# Main.net
KiCad netlist of a schematic drawn in Altium Designer
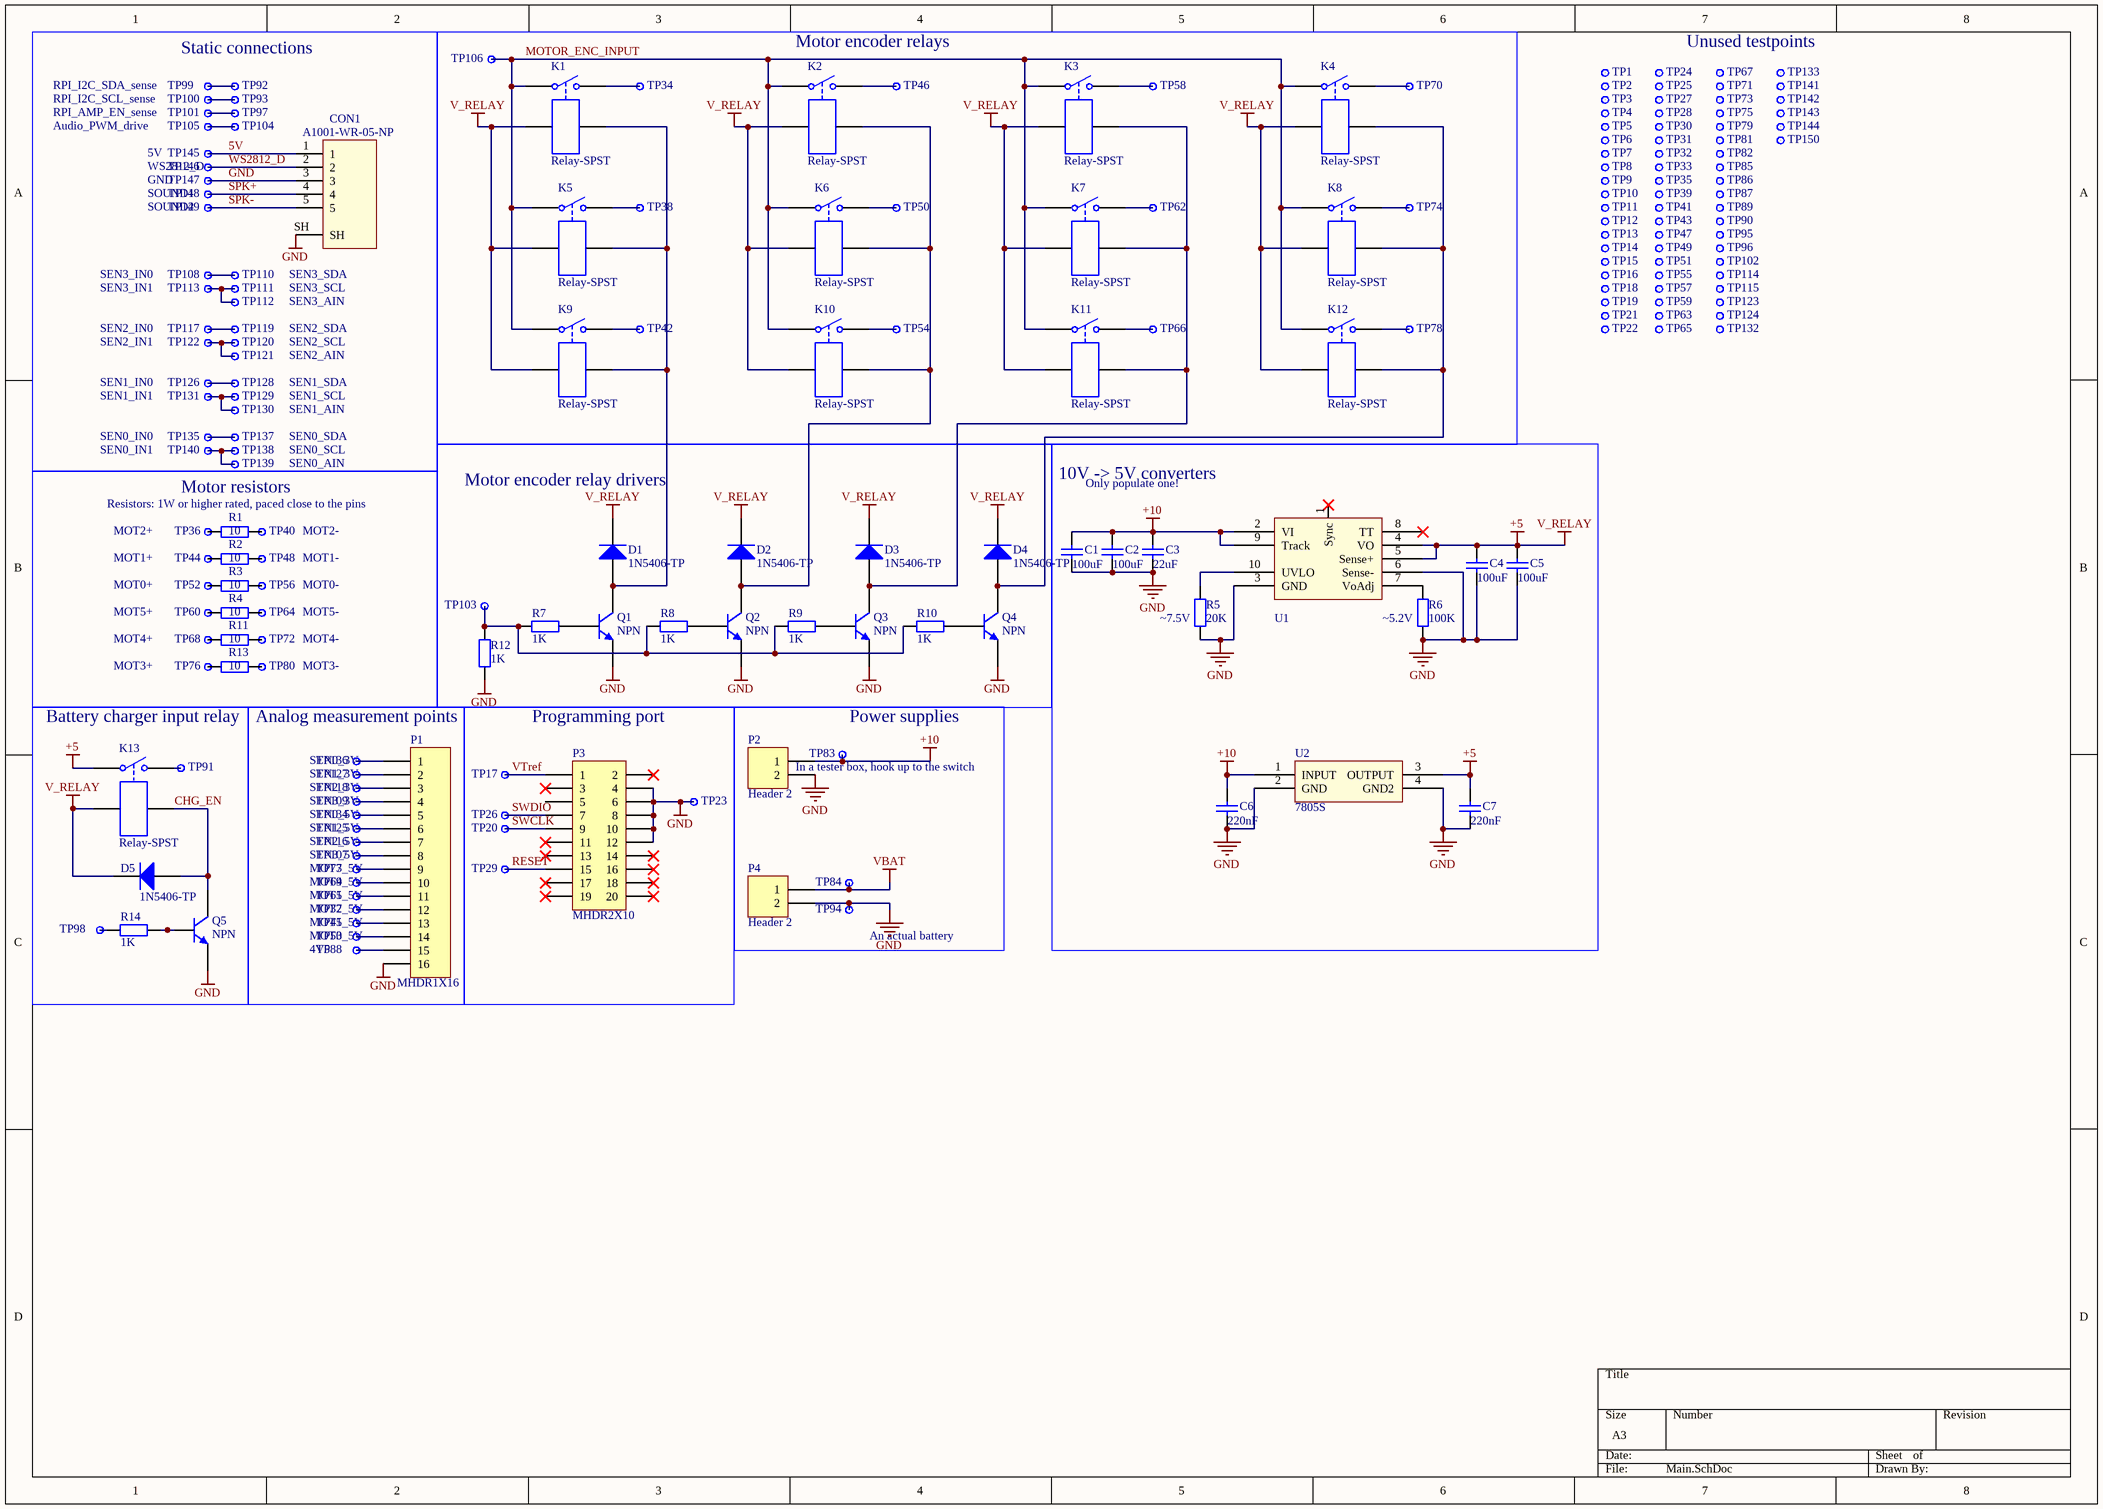
[diagram p0: Main.SchDoc]

(export (version "E")
  (design (tool "Eeschema 10.0.6"))
  (components
    (comp (ref "C1")
      (value "100uF")
      (footprint "C3216")
      (description "Capacitor")
      (fields (field (name "PARTNUMBER") "CL31A107MPKNNWE") (field (name "PUBLISHER") "Altium Limited"))
      (libsource (lib "Miscellaneous Devices") (part "Cap"))
    )
    (comp (ref "C2")
      (value "100uF")
      (footprint "C3216")
      (description "Capacitor")
      (fields (field (name "PARTNUMBER") "CL31A107MPKNNWE") (field (name "PUBLISHER") "Altium Limited"))
      (libsource (lib "Miscellaneous Devices") (part "Cap"))
    )
    (comp (ref "C3")
      (value "22uF")
      (footprint "6-0805_N")
      (description "Capacitor")
      (fields (field (name "Comment") "Cap") (field (name "PUBLISHER") "Altium Limited"))
      (libsource (lib "Miscellaneous Devices") (part "Cap"))
    )
    (comp (ref "C4")
      (value "100uF")
      (footprint "C3216")
      (description "Capacitor")
      (fields (field (name "PARTNUMBER") "CL31A107MPKNNWE") (field (name "PUBLISHER") "Altium Limited"))
      (libsource (lib "Miscellaneous Devices") (part "Cap"))
    )
    (comp (ref "C5")
      (value "100uF")
      (footprint "C3216")
      (description "Capacitor")
      (fields (field (name "PARTNUMBER") "CL31A107MPKNNWE") (field (name "PUBLISHER") "Altium Limited"))
      (libsource (lib "Miscellaneous Devices") (part "Cap"))
    )
    (comp (ref "C6")
      (value "220nF")
      (footprint "6-0805_N")
      (description "Capacitor")
      (fields (field (name "Comment") "Cap") (field (name "PUBLISHER") "Altium Limited"))
      (libsource (lib "Miscellaneous Devices") (part "Cap"))
    )
    (comp (ref "C7")
      (value "220nF")
      (footprint "6-0805_N")
      (description "Capacitor")
      (fields (field (name "Comment") "Cap") (field (name "PUBLISHER") "Altium Limited"))
      (libsource (lib "Miscellaneous Devices") (part "Cap"))
    )
    (comp (ref "CON1")
      (value "A1001-WR-05-NP")
      (footprint "LED molex")
      (libsource (lib "parts") (part "LED molex"))
    )
    (comp (ref "D1")
      (value "1N5406-TP")
      (footprint "DO-201AD")
      (fields (field (name "PUBLISHER") "Altium Limited"))
      (libsource (lib "Miscellaneous Devices") (part "Diode"))
    )
    (comp (ref "D2")
      (value "1N5406-TP")
      (footprint "DO-201AD")
      (fields (field (name "PUBLISHER") "Altium Limited"))
      (libsource (lib "Miscellaneous Devices") (part "Diode"))
    )
    (comp (ref "D3")
      (value "1N5406-TP")
      (footprint "DO-201AD")
      (fields (field (name "PUBLISHER") "Altium Limited"))
      (libsource (lib "Miscellaneous Devices") (part "Diode"))
    )
    (comp (ref "D4")
      (value "1N5406-TP")
      (footprint "DO-201AD")
      (fields (field (name "PUBLISHER") "Altium Limited"))
      (libsource (lib "Miscellaneous Devices") (part "Diode"))
    )
    (comp (ref "D5")
      (value "1N5406-TP")
      (footprint "DO-201AD")
      (fields (field (name "PUBLISHER") "Altium Limited"))
      (libsource (lib "Miscellaneous Devices") (part "Diode"))
    )
    (comp (ref "K1")
      (value "Relay-SPST")
      (footprint "AHQSH105LM100G")
      (description "Single-Pole Single-Throw Relay")
      (fields (field (name "PUBLISHER") "Altium Limited"))
      (libsource (lib "Miscellaneous Devices") (part "Relay-SPST"))
    )
    (comp (ref "K2")
      (value "Relay-SPST")
      (footprint "AHQSH105LM100G")
      (description "Single-Pole Single-Throw Relay")
      (fields (field (name "PUBLISHER") "Altium Limited"))
      (libsource (lib "Miscellaneous Devices") (part "Relay-SPST"))
    )
    (comp (ref "K3")
      (value "Relay-SPST")
      (footprint "AHQSH105LM100G")
      (description "Single-Pole Single-Throw Relay")
      (fields (field (name "PUBLISHER") "Altium Limited"))
      (libsource (lib "Miscellaneous Devices") (part "Relay-SPST"))
    )
    (comp (ref "K4")
      (value "Relay-SPST")
      (footprint "AHQSH105LM100G")
      (description "Single-Pole Single-Throw Relay")
      (fields (field (name "PUBLISHER") "Altium Limited"))
      (libsource (lib "Miscellaneous Devices") (part "Relay-SPST"))
    )
    (comp (ref "K5")
      (value "Relay-SPST")
      (footprint "AHQSH105LM100G")
      (description "Single-Pole Single-Throw Relay")
      (fields (field (name "PUBLISHER") "Altium Limited"))
      (libsource (lib "Miscellaneous Devices") (part "Relay-SPST"))
    )
    (comp (ref "K6")
      (value "Relay-SPST")
      (footprint "AHQSH105LM100G")
      (description "Single-Pole Single-Throw Relay")
      (fields (field (name "PUBLISHER") "Altium Limited"))
      (libsource (lib "Miscellaneous Devices") (part "Relay-SPST"))
    )
    (comp (ref "K7")
      (value "Relay-SPST")
      (footprint "AHQSH105LM100G")
      (description "Single-Pole Single-Throw Relay")
      (fields (field (name "PUBLISHER") "Altium Limited"))
      (libsource (lib "Miscellaneous Devices") (part "Relay-SPST"))
    )
    (comp (ref "K8")
      (value "Relay-SPST")
      (footprint "AHQSH105LM100G")
      (description "Single-Pole Single-Throw Relay")
      (fields (field (name "PUBLISHER") "Altium Limited"))
      (libsource (lib "Miscellaneous Devices") (part "Relay-SPST"))
    )
    (comp (ref "K9")
      (value "Relay-SPST")
      (footprint "AHQSH105LM100G")
      (description "Single-Pole Single-Throw Relay")
      (fields (field (name "PUBLISHER") "Altium Limited"))
      (libsource (lib "Miscellaneous Devices") (part "Relay-SPST"))
    )
    (comp (ref "K10")
      (value "Relay-SPST")
      (footprint "AHQSH105LM100G")
      (description "Single-Pole Single-Throw Relay")
      (fields (field (name "PUBLISHER") "Altium Limited"))
      (libsource (lib "Miscellaneous Devices") (part "Relay-SPST"))
    )
    (comp (ref "K11")
      (value "Relay-SPST")
      (footprint "AHQSH105LM100G")
      (description "Single-Pole Single-Throw Relay")
      (fields (field (name "PUBLISHER") "Altium Limited"))
      (libsource (lib "Miscellaneous Devices") (part "Relay-SPST"))
    )
    (comp (ref "K12")
      (value "Relay-SPST")
      (footprint "AHQSH105LM100G")
      (description "Single-Pole Single-Throw Relay")
      (fields (field (name "PUBLISHER") "Altium Limited"))
      (libsource (lib "Miscellaneous Devices") (part "Relay-SPST"))
    )
    (comp (ref "K13")
      (value "Relay-SPST")
      (footprint "AHQSH105LM100G")
      (description "Single-Pole Single-Throw Relay")
      (fields (field (name "PUBLISHER") "Altium Limited"))
      (libsource (lib "Miscellaneous Devices") (part "Relay-SPST"))
    )
    (comp (ref "P1")
      (value "MHDR1X16")
      (footprint "MHDR1X16")
      (description "Header, 16-Pin")
      (fields (field (name "PUBLISHER") "Altium Limited"))
      (libsource (lib "Miscellaneous Connectors") (part "MHDR1X16"))
    )
    (comp (ref "P2")
      (value "Header 2")
      (footprint "HDR1X2")
      (description "Header, 2-Pin")
      (fields (field (name "PUBLISHER") "Altium Limited"))
      (libsource (lib "Miscellaneous Connectors") (part "Header 2"))
    )
    (comp (ref "P3")
      (value "MHDR2X10")
      (footprint "MHDR2X10")
      (description "Header, 10-Pin, Dual row")
      (fields (field (name "PUBLISHER") "Altium Limited"))
      (libsource (lib "Miscellaneous Connectors") (part "MHDR2X10"))
    )
    (comp (ref "P4")
      (value "Header 2")
      (footprint "HDR1X2")
      (description "Header, 2-Pin")
      (fields (field (name "PUBLISHER") "Altium Limited"))
      (libsource (lib "Miscellaneous Connectors") (part "Header 2"))
    )
    (comp (ref "Q1")
      (value "NPN")
      (footprint "SOT-23_N")
      (description "NPN Bipolar Transistor MMBT2222A")
      (fields (field (name "PART NUMBER") "MMBT2222A") (field (name "PUBLISHER") "Altium Limited"))
      (libsource (lib "Miscellaneous Devices") (part "NPN"))
    )
    (comp (ref "Q2")
      (value "NPN")
      (footprint "SOT-23_N")
      (description "NPN Bipolar Transistor MMBT2222A")
      (fields (field (name "PART NUMBER") "MMBT2222A") (field (name "PUBLISHER") "Altium Limited"))
      (libsource (lib "Miscellaneous Devices") (part "NPN"))
    )
    (comp (ref "Q3")
      (value "NPN")
      (footprint "SOT-23_N")
      (description "NPN Bipolar Transistor MMBT2222A")
      (fields (field (name "PART NUMBER") "MMBT2222A") (field (name "PUBLISHER") "Altium Limited"))
      (libsource (lib "Miscellaneous Devices") (part "NPN"))
    )
    (comp (ref "Q4")
      (value "NPN")
      (footprint "SOT-23_N")
      (description "NPN Bipolar Transistor MMBT2222A")
      (fields (field (name "PART NUMBER") "MMBT2222A") (field (name "PUBLISHER") "Altium Limited"))
      (libsource (lib "Miscellaneous Devices") (part "NPN"))
    )
    (comp (ref "Q5")
      (value "NPN")
      (footprint "SOT-23_N")
      (description "NPN Bipolar Transistor MMBT2222A")
      (fields (field (name "PART NUMBER") "MMBT2222A") (field (name "PUBLISHER") "Altium Limited"))
      (libsource (lib "Miscellaneous Devices") (part "NPN"))
    )
    (comp (ref "R1")
      (value "10")
      (footprint "AXIAL-0.7")
      (description "Resistor EP5WS10RJ 10R 5W")
      (fields
        (field (name "PARTNUMBER") "EP5WS10RJ")
        (field (name "Comment") "Res2")
        (field (name "PUBLISHER") "Altium Limited")
      )
      (libsource (lib "Miscellaneous Devices") (part "Res2"))
    )
    (comp (ref "R2")
      (value "10")
      (footprint "AXIAL-0.7")
      (description "Resistor EP5WS10RJ 10R 5W")
      (fields
        (field (name "PARTNUMBER") "EP5WS10RJ")
        (field (name "Comment") "Res2")
        (field (name "PUBLISHER") "Altium Limited")
      )
      (libsource (lib "Miscellaneous Devices") (part "Res2"))
    )
    (comp (ref "R3")
      (value "10")
      (footprint "AXIAL-0.7")
      (description "Resistor EP5WS10RJ 10R 5W")
      (fields
        (field (name "PARTNUMBER") "EP5WS10RJ")
        (field (name "Comment") "Res2")
        (field (name "PUBLISHER") "Altium Limited")
      )
      (libsource (lib "Miscellaneous Devices") (part "Res2"))
    )
    (comp (ref "R4")
      (value "10")
      (footprint "AXIAL-0.7")
      (description "Resistor EP5WS10RJ 10R 5W")
      (fields
        (field (name "PARTNUMBER") "EP5WS10RJ")
        (field (name "Comment") "Res2")
        (field (name "PUBLISHER") "Altium Limited")
      )
      (libsource (lib "Miscellaneous Devices") (part "Res2"))
    )
    (comp (ref "R5")
      (value "20K")
      (footprint "1608[0603]")
      (description "Resistor")
      (fields (field (name "Comment") "Res2") (field (name "PUBLISHER") "Altium Limited"))
      (libsource (lib "") (part "Res2_1"))
    )
    (comp (ref "R6")
      (value "100K")
      (footprint "1608[0603]")
      (description "Resistor")
      (fields (field (name "Comment") "Res2") (field (name "PUBLISHER") "Altium Limited"))
      (libsource (lib "") (part "Res2_1"))
    )
    (comp (ref "R7")
      (value "1K")
      (footprint "1608[0603]")
      (description "Resistor")
      (fields (field (name "Comment") "Res2") (field (name "PUBLISHER") "Altium Limited"))
      (libsource (lib "Miscellaneous Devices") (part "Res2"))
    )
    (comp (ref "R8")
      (value "1K")
      (footprint "1608[0603]")
      (description "Resistor")
      (fields (field (name "Comment") "Res2") (field (name "PUBLISHER") "Altium Limited"))
      (libsource (lib "Miscellaneous Devices") (part "Res2"))
    )
    (comp (ref "R9")
      (value "1K")
      (footprint "1608[0603]")
      (description "Resistor")
      (fields (field (name "Comment") "Res2") (field (name "PUBLISHER") "Altium Limited"))
      (libsource (lib "Miscellaneous Devices") (part "Res2"))
    )
    (comp (ref "R10")
      (value "1K")
      (footprint "1608[0603]")
      (description "Resistor")
      (fields (field (name "Comment") "Res2") (field (name "PUBLISHER") "Altium Limited"))
      (libsource (lib "Miscellaneous Devices") (part "Res2"))
    )
    (comp (ref "R11")
      (value "10")
      (footprint "AXIAL-0.7")
      (description "Resistor EP5WS10RJ 10R 5W")
      (fields
        (field (name "PARTNUMBER") "EP5WS10RJ")
        (field (name "Comment") "Res2")
        (field (name "PUBLISHER") "Altium Limited")
      )
      (libsource (lib "Miscellaneous Devices") (part "Res2"))
    )
    (comp (ref "R12")
      (value "1K")
      (footprint "1608[0603]")
      (description "Resistor")
      (fields (field (name "Comment") "Res2") (field (name "PUBLISHER") "Altium Limited"))
      (libsource (lib "") (part "Res2_1"))
    )
    (comp (ref "R13")
      (value "10")
      (footprint "AXIAL-0.7")
      (description "Resistor EP5WS10RJ 10R 5W")
      (fields
        (field (name "PARTNUMBER") "EP5WS10RJ")
        (field (name "Comment") "Res2")
        (field (name "PUBLISHER") "Altium Limited")
      )
      (libsource (lib "Miscellaneous Devices") (part "Res2"))
    )
    (comp (ref "R14")
      (value "1K")
      (footprint "1608[0603]")
      (description "Resistor")
      (fields (field (name "Comment") "Res2") (field (name "PUBLISHER") "Altium Limited"))
      (libsource (lib "Miscellaneous Devices") (part "Res2"))
    )
    (comp (ref "TP1")
      (value "Pin")
      (footprint "Pin")
      (description "Testing pin")
      (libsource (lib "parts") (part "Pin"))
    )
    (comp (ref "TP2")
      (value "Pin")
      (footprint "Pin")
      (description "Testing pin")
      (libsource (lib "parts") (part "Pin"))
    )
    (comp (ref "TP3")
      (value "Pin")
      (footprint "Pin")
      (description "Testing pin")
      (libsource (lib "parts") (part "Pin"))
    )
    (comp (ref "TP4")
      (value "Pin")
      (footprint "Pin")
      (description "Testing pin")
      (libsource (lib "parts") (part "Pin"))
    )
    (comp (ref "TP5")
      (value "Pin")
      (footprint "Pin")
      (description "Testing pin")
      (libsource (lib "parts") (part "Pin"))
    )
    (comp (ref "TP6")
      (value "Pin")
      (footprint "Pin")
      (description "Testing pin")
      (libsource (lib "parts") (part "Pin"))
    )
    (comp (ref "TP7")
      (value "Pin")
      (footprint "Pin")
      (description "Testing pin")
      (libsource (lib "parts") (part "Pin"))
    )
    (comp (ref "TP8")
      (value "Pin")
      (footprint "Pin")
      (description "Testing pin")
      (libsource (lib "parts") (part "Pin"))
    )
    (comp (ref "TP9")
      (value "Pin")
      (footprint "Pin")
      (description "Testing pin")
      (libsource (lib "parts") (part "Pin"))
    )
    (comp (ref "TP10")
      (value "Pin")
      (footprint "Pin")
      (description "Testing pin")
      (libsource (lib "parts") (part "Pin"))
    )
    (comp (ref "TP11")
      (value "Pin")
      (footprint "Pin")
      (description "Testing pin")
      (libsource (lib "parts") (part "Pin"))
    )
    (comp (ref "TP12")
      (value "Pin")
      (footprint "Pin")
      (description "Testing pin")
      (libsource (lib "parts") (part "Pin"))
    )
    (comp (ref "TP13")
      (value "Pin")
      (footprint "Pin")
      (description "Testing pin")
      (libsource (lib "parts") (part "Pin"))
    )
    (comp (ref "TP14")
      (value "Pin")
      (footprint "Pin")
      (description "Testing pin")
      (libsource (lib "parts") (part "Pin"))
    )
    (comp (ref "TP15")
      (value "Pin")
      (footprint "Pin")
      (description "Testing pin")
      (libsource (lib "parts") (part "Pin"))
    )
    (comp (ref "TP16")
      (value "Pin")
      (footprint "Pin")
      (description "Testing pin")
      (libsource (lib "parts") (part "Pin"))
    )
    (comp (ref "TP17")
      (value "Pin")
      (footprint "Pin")
      (description "Testing pin")
      (libsource (lib "parts") (part "Pin"))
    )
    (comp (ref "TP18")
      (value "Pin")
      (footprint "Pin")
      (description "Testing pin")
      (libsource (lib "parts") (part "Pin"))
    )
    (comp (ref "TP19")
      (value "Pin")
      (footprint "Pin")
      (description "Testing pin")
      (libsource (lib "parts") (part "Pin"))
    )
    (comp (ref "TP20")
      (value "Pin")
      (footprint "Pin")
      (description "Testing pin")
      (libsource (lib "parts") (part "Pin"))
    )
    (comp (ref "TP21")
      (value "Pin")
      (footprint "Pin")
      (description "Testing pin")
      (libsource (lib "parts") (part "Pin"))
    )
    (comp (ref "TP22")
      (value "Pin")
      (footprint "Pin")
      (description "Testing pin")
      (libsource (lib "parts") (part "Pin"))
    )
    (comp (ref "TP23")
      (value "Pin")
      (footprint "Pin")
      (description "Testing pin")
      (libsource (lib "parts") (part "Pin"))
    )
    (comp (ref "TP24")
      (value "Pin")
      (footprint "Pin")
      (description "Testing pin")
      (libsource (lib "parts") (part "Pin"))
    )
    (comp (ref "TP25")
      (value "Pin")
      (footprint "Pin")
      (description "Testing pin")
      (libsource (lib "parts") (part "Pin"))
    )
    (comp (ref "TP26")
      (value "Pin")
      (footprint "Pin")
      (description "Testing pin")
      (libsource (lib "parts") (part "Pin"))
    )
    (comp (ref "TP27")
      (value "Pin")
      (footprint "Pin")
      (description "Testing pin")
      (libsource (lib "parts") (part "Pin"))
    )
    (comp (ref "TP28")
      (value "Pin")
      (footprint "Pin")
      (description "Testing pin")
      (libsource (lib "parts") (part "Pin"))
    )
    (comp (ref "TP29")
      (value "Pin")
      (footprint "Pin")
      (description "Testing pin")
      (libsource (lib "parts") (part "Pin"))
    )
    (comp (ref "TP30")
      (value "Pin")
      (footprint "Pin")
      (description "Testing pin")
      (libsource (lib "parts") (part "Pin"))
    )
    (comp (ref "TP31")
      (value "Pin")
      (footprint "Pin")
      (description "Testing pin")
      (libsource (lib "parts") (part "Pin"))
    )
    (comp (ref "TP32")
      (value "Pin")
      (footprint "Pin")
      (description "Testing pin")
      (libsource (lib "parts") (part "Pin"))
    )
    (comp (ref "TP33")
      (value "Pin")
      (footprint "Pin")
      (description "Testing pin")
      (libsource (lib "parts") (part "Pin"))
    )
    (comp (ref "TP34")
      (value "Pin")
      (footprint "Pin")
      (description "Testing pin")
      (libsource (lib "parts") (part "Pin"))
    )
    (comp (ref "TP35")
      (value "Pin")
      (footprint "Pin")
      (description "Testing pin")
      (libsource (lib "parts") (part "Pin"))
    )
    (comp (ref "TP36")
      (value "Pin")
      (footprint "Pin")
      (description "Testing pin")
      (libsource (lib "parts") (part "Pin"))
    )
    (comp (ref "TP37")
      (value "Pin")
      (footprint "Pin")
      (description "Testing pin")
      (libsource (lib "parts") (part "Pin"))
    )
    (comp (ref "TP38")
      (value "Pin")
      (footprint "Pin")
      (description "Testing pin")
      (libsource (lib "parts") (part "Pin"))
    )
    (comp (ref "TP39")
      (value "Pin")
      (footprint "Pin")
      (description "Testing pin")
      (libsource (lib "parts") (part "Pin"))
    )
    (comp (ref "TP40")
      (value "Pin")
      (footprint "Pin")
      (description "Testing pin")
      (libsource (lib "parts") (part "Pin"))
    )
    (comp (ref "TP41")
      (value "Pin")
      (footprint "Pin")
      (description "Testing pin")
      (libsource (lib "parts") (part "Pin"))
    )
    (comp (ref "TP42")
      (value "Pin")
      (footprint "Pin")
      (description "Testing pin")
      (libsource (lib "parts") (part "Pin"))
    )
    (comp (ref "TP43")
      (value "Pin")
      (footprint "Pin")
      (description "Testing pin")
      (libsource (lib "parts") (part "Pin"))
    )
    (comp (ref "TP44")
      (value "Pin")
      (footprint "Pin")
      (description "Testing pin")
      (libsource (lib "parts") (part "Pin"))
    )
    (comp (ref "TP45")
      (value "Pin")
      (footprint "Pin")
      (description "Testing pin")
      (libsource (lib "parts") (part "Pin"))
    )
    (comp (ref "TP46")
      (value "Pin")
      (footprint "Pin")
      (description "Testing pin")
      (libsource (lib "parts") (part "Pin"))
    )
    (comp (ref "TP47")
      (value "Pin")
      (footprint "Pin")
      (description "Testing pin")
      (libsource (lib "parts") (part "Pin"))
    )
    (comp (ref "TP48")
      (value "Pin")
      (footprint "Pin")
      (description "Testing pin")
      (libsource (lib "parts") (part "Pin"))
    )
    (comp (ref "TP49")
      (value "Pin")
      (footprint "Pin")
      (description "Testing pin")
      (libsource (lib "parts") (part "Pin"))
    )
    (comp (ref "TP50")
      (value "Pin")
      (footprint "Pin")
      (description "Testing pin")
      (libsource (lib "parts") (part "Pin"))
    )
    (comp (ref "TP51")
      (value "Pin")
      (footprint "Pin")
      (description "Testing pin")
      (libsource (lib "parts") (part "Pin"))
    )
    (comp (ref "TP52")
      (value "Pin")
      (footprint "Pin")
      (description "Testing pin")
      (libsource (lib "parts") (part "Pin"))
    )
    (comp (ref "TP53")
      (value "Pin")
      (footprint "Pin")
      (description "Testing pin")
      (libsource (lib "parts") (part "Pin"))
    )
    (comp (ref "TP54")
      (value "Pin")
      (footprint "Pin")
      (description "Testing pin")
      (libsource (lib "parts") (part "Pin"))
    )
    (comp (ref "TP55")
      (value "Pin")
      (footprint "Pin")
      (description "Testing pin")
      (libsource (lib "parts") (part "Pin"))
    )
    (comp (ref "TP56")
      (value "Pin")
      (footprint "Pin")
      (description "Testing pin")
      (libsource (lib "parts") (part "Pin"))
    )
    (comp (ref "TP57")
      (value "Pin")
      (footprint "Pin")
      (description "Testing pin")
      (libsource (lib "parts") (part "Pin"))
    )
    (comp (ref "TP58")
      (value "Pin")
      (footprint "Pin")
      (description "Testing pin")
      (libsource (lib "parts") (part "Pin"))
    )
    (comp (ref "TP59")
      (value "Pin")
      (footprint "Pin")
      (description "Testing pin")
      (libsource (lib "parts") (part "Pin"))
    )
    (comp (ref "TP60")
      (value "Pin")
      (footprint "Pin")
      (description "Testing pin")
      (libsource (lib "parts") (part "Pin"))
    )
    (comp (ref "TP61")
      (value "Pin")
      (footprint "Pin")
      (description "Testing pin")
      (libsource (lib "parts") (part "Pin"))
    )
    (comp (ref "TP62")
      (value "Pin")
      (footprint "Pin")
      (description "Testing pin")
      (libsource (lib "parts") (part "Pin"))
    )
    (comp (ref "TP63")
      (value "Pin")
      (footprint "Pin")
      (description "Testing pin")
      (libsource (lib "parts") (part "Pin"))
    )
    (comp (ref "TP64")
      (value "Pin")
      (footprint "Pin")
      (description "Testing pin")
      (libsource (lib "parts") (part "Pin"))
    )
    (comp (ref "TP65")
      (value "Pin")
      (footprint "Pin")
      (description "Testing pin")
      (libsource (lib "parts") (part "Pin"))
    )
    (comp (ref "TP66")
      (value "Pin")
      (footprint "Pin")
      (description "Testing pin")
      (libsource (lib "parts") (part "Pin"))
    )
    (comp (ref "TP67")
      (value "Pin")
      (footprint "Pin")
      (description "Testing pin")
      (libsource (lib "parts") (part "Pin"))
    )
    (comp (ref "TP68")
      (value "Pin")
      (footprint "Pin")
      (description "Testing pin")
      (libsource (lib "parts") (part "Pin"))
    )
    (comp (ref "TP69")
      (value "Pin")
      (footprint "Pin")
      (description "Testing pin")
      (libsource (lib "parts") (part "Pin"))
    )
    (comp (ref "TP70")
      (value "Pin")
      (footprint "Pin")
      (description "Testing pin")
      (libsource (lib "parts") (part "Pin"))
    )
    (comp (ref "TP71")
      (value "Pin")
      (footprint "Pin")
      (description "Testing pin")
      (libsource (lib "parts") (part "Pin"))
    )
    (comp (ref "TP72")
      (value "Pin")
      (footprint "Pin")
      (description "Testing pin")
      (libsource (lib "parts") (part "Pin"))
    )
    (comp (ref "TP73")
      (value "Pin")
      (footprint "Pin")
      (description "Testing pin")
      (libsource (lib "parts") (part "Pin"))
    )
    (comp (ref "TP74")
      (value "Pin")
      (footprint "Pin")
      (description "Testing pin")
      (libsource (lib "parts") (part "Pin"))
    )
    (comp (ref "TP75")
      (value "Pin")
      (footprint "Pin")
      (description "Testing pin")
      (libsource (lib "parts") (part "Pin"))
    )
    (comp (ref "TP76")
      (value "Pin")
      (footprint "Pin")
      (description "Testing pin")
      (libsource (lib "parts") (part "Pin"))
    )
    (comp (ref "TP77")
      (value "Pin")
      (footprint "Pin")
      (description "Testing pin")
      (libsource (lib "parts") (part "Pin"))
    )
    (comp (ref "TP78")
      (value "Pin")
      (footprint "Pin")
      (description "Testing pin")
      (libsource (lib "parts") (part "Pin"))
    )
    (comp (ref "TP79")
      (value "Pin")
      (footprint "Pin")
      (description "Testing pin")
      (libsource (lib "parts") (part "Pin"))
    )
    (comp (ref "TP80")
      (value "Pin")
      (footprint "Pin")
      (description "Testing pin")
      (libsource (lib "parts") (part "Pin"))
    )
    (comp (ref "TP81")
      (value "Pin")
      (footprint "Pin")
      (description "Testing pin")
      (libsource (lib "parts") (part "Pin"))
    )
    (comp (ref "TP82")
      (value "Pin")
      (footprint "Pin")
      (description "Testing pin")
      (libsource (lib "parts") (part "Pin"))
    )
    (comp (ref "TP83")
      (value "Pin")
      (footprint "Pin")
      (description "Testing pin")
      (libsource (lib "parts") (part "Pin"))
    )
    (comp (ref "TP84")
      (value "Pin")
      (footprint "Pin")
      (description "Testing pin")
      (libsource (lib "parts") (part "Pin"))
    )
    (comp (ref "TP85")
      (value "Pin")
      (footprint "Pin")
      (description "Testing pin")
      (libsource (lib "parts") (part "Pin"))
    )
    (comp (ref "TP86")
      (value "Pin")
      (footprint "Pin")
      (description "Testing pin")
      (libsource (lib "parts") (part "Pin"))
    )
    (comp (ref "TP87")
      (value "Pin")
      (footprint "Pin")
      (description "Testing pin")
      (libsource (lib "parts") (part "Pin"))
    )
    (comp (ref "TP88")
      (value "Pin")
      (footprint "Pin")
      (description "Testing pin")
      (libsource (lib "parts") (part "Pin"))
    )
    (comp (ref "TP89")
      (value "Pin")
      (footprint "Pin")
      (description "Testing pin")
      (libsource (lib "parts") (part "Pin"))
    )
    (comp (ref "TP90")
      (value "Pin")
      (footprint "Pin")
      (description "Testing pin")
      (libsource (lib "parts") (part "Pin"))
    )
    (comp (ref "TP91")
      (value "Pin")
      (footprint "Pin")
      (description "Testing pin")
      (libsource (lib "parts") (part "Pin"))
    )
    (comp (ref "TP92")
      (value "Pin")
      (footprint "Pin")
      (description "Testing pin")
      (libsource (lib "parts") (part "Pin"))
    )
    (comp (ref "TP93")
      (value "Pin")
      (footprint "Pin")
      (description "Testing pin")
      (libsource (lib "parts") (part "Pin"))
    )
    (comp (ref "TP94")
      (value "Pin")
      (footprint "Pin")
      (description "Testing pin")
      (libsource (lib "parts") (part "Pin"))
    )
    (comp (ref "TP95")
      (value "Pin")
      (footprint "Pin")
      (description "Testing pin")
      (libsource (lib "parts") (part "Pin"))
    )
    (comp (ref "TP96")
      (value "Pin")
      (footprint "Pin")
      (description "Testing pin")
      (libsource (lib "parts") (part "Pin"))
    )
    (comp (ref "TP97")
      (value "Pin")
      (footprint "Pin")
      (description "Testing pin")
      (libsource (lib "parts") (part "Pin"))
    )
    (comp (ref "TP98")
      (value "Pin")
      (footprint "Pin")
      (description "Testing pin")
      (libsource (lib "parts") (part "Pin"))
    )
    (comp (ref "TP99")
      (value "Pin")
      (footprint "Pin")
      (description "Testing pin")
      (libsource (lib "parts") (part "Pin"))
    )
    (comp (ref "TP100")
      (value "Pin")
      (footprint "Pin")
      (description "Testing pin")
      (libsource (lib "parts") (part "Pin"))
    )
    (comp (ref "TP101")
      (value "Pin")
      (footprint "Pin")
      (description "Testing pin")
      (libsource (lib "parts") (part "Pin"))
    )
    (comp (ref "TP102")
      (value "Pin")
      (footprint "Pin")
      (description "Testing pin")
      (libsource (lib "parts") (part "Pin"))
    )
    (comp (ref "TP103")
      (value "Pin")
      (footprint "Pin")
      (description "Testing pin")
      (libsource (lib "parts") (part "Pin"))
    )
    (comp (ref "TP104")
      (value "Pin")
      (footprint "Pin")
      (description "Testing pin")
      (libsource (lib "parts") (part "Pin"))
    )
    (comp (ref "TP105")
      (value "Pin")
      (footprint "Pin")
      (description "Testing pin")
      (libsource (lib "parts") (part "Pin"))
    )
    (comp (ref "TP106")
      (value "Pin")
      (footprint "Pin")
      (description "Testing pin")
      (libsource (lib "parts") (part "Pin"))
    )
    (comp (ref "TP107")
      (value "Pin")
      (footprint "Pin")
      (description "Testing pin")
      (libsource (lib "parts") (part "Pin"))
    )
    (comp (ref "TP108")
      (value "Pin")
      (footprint "Pin")
      (description "Testing pin")
      (libsource (lib "parts") (part "Pin"))
    )
    (comp (ref "TP109")
      (value "Pin")
      (footprint "Pin")
      (description "Testing pin")
      (libsource (lib "parts") (part "Pin"))
    )
    (comp (ref "TP110")
      (value "Pin")
      (footprint "Pin")
      (description "Testing pin")
      (libsource (lib "parts") (part "Pin"))
    )
    (comp (ref "TP111")
      (value "Pin")
      (footprint "Pin")
      (description "Testing pin")
      (libsource (lib "parts") (part "Pin"))
    )
    (comp (ref "TP112")
      (value "Pin")
      (footprint "Pin")
      (description "Testing pin")
      (libsource (lib "parts") (part "Pin"))
    )
    (comp (ref "TP113")
      (value "Pin")
      (footprint "Pin")
      (description "Testing pin")
      (libsource (lib "parts") (part "Pin"))
    )
    (comp (ref "TP114")
      (value "Pin")
      (footprint "Pin")
      (description "Testing pin")
      (libsource (lib "parts") (part "Pin"))
    )
    (comp (ref "TP115")
      (value "Pin")
      (footprint "Pin")
      (description "Testing pin")
      (libsource (lib "parts") (part "Pin"))
    )
    (comp (ref "TP116")
      (value "Pin")
      (footprint "Pin")
      (description "Testing pin")
      (libsource (lib "parts") (part "Pin"))
    )
    (comp (ref "TP117")
      (value "Pin")
      (footprint "Pin")
      (description "Testing pin")
      (libsource (lib "parts") (part "Pin"))
    )
    (comp (ref "TP118")
      (value "Pin")
      (footprint "Pin")
      (description "Testing pin")
      (libsource (lib "parts") (part "Pin"))
    )
    (comp (ref "TP119")
      (value "Pin")
      (footprint "Pin")
      (description "Testing pin")
      (libsource (lib "parts") (part "Pin"))
    )
    (comp (ref "TP120")
      (value "Pin")
      (footprint "Pin")
      (description "Testing pin")
      (libsource (lib "parts") (part "Pin"))
    )
    (comp (ref "TP121")
      (value "Pin")
      (footprint "Pin")
      (description "Testing pin")
      (libsource (lib "parts") (part "Pin"))
    )
    (comp (ref "TP122")
      (value "Pin")
      (footprint "Pin")
      (description "Testing pin")
      (libsource (lib "parts") (part "Pin"))
    )
    (comp (ref "TP123")
      (value "Pin")
      (footprint "Pin")
      (description "Testing pin")
      (libsource (lib "parts") (part "Pin"))
    )
    (comp (ref "TP124")
      (value "Pin")
      (footprint "Pin")
      (description "Testing pin")
      (libsource (lib "parts") (part "Pin"))
    )
    (comp (ref "TP125")
      (value "Pin")
      (footprint "Pin")
      (description "Testing pin")
      (libsource (lib "parts") (part "Pin"))
    )
    (comp (ref "TP126")
      (value "Pin")
      (footprint "Pin")
      (description "Testing pin")
      (libsource (lib "parts") (part "Pin"))
    )
    (comp (ref "TP127")
      (value "Pin")
      (footprint "Pin")
      (description "Testing pin")
      (libsource (lib "parts") (part "Pin"))
    )
    (comp (ref "TP128")
      (value "Pin")
      (footprint "Pin")
      (description "Testing pin")
      (libsource (lib "parts") (part "Pin"))
    )
    (comp (ref "TP129")
      (value "Pin")
      (footprint "Pin")
      (description "Testing pin")
      (libsource (lib "parts") (part "Pin"))
    )
    (comp (ref "TP130")
      (value "Pin")
      (footprint "Pin")
      (description "Testing pin")
      (libsource (lib "parts") (part "Pin"))
    )
    (comp (ref "TP131")
      (value "Pin")
      (footprint "Pin")
      (description "Testing pin")
      (libsource (lib "parts") (part "Pin"))
    )
    (comp (ref "TP132")
      (value "Pin")
      (footprint "Pin")
      (description "Testing pin")
      (libsource (lib "parts") (part "Pin"))
    )
    (comp (ref "TP133")
      (value "Pin")
      (footprint "Pin")
      (description "Testing pin")
      (libsource (lib "parts") (part "Pin"))
    )
    (comp (ref "TP134")
      (value "Pin")
      (footprint "Pin")
      (description "Testing pin")
      (libsource (lib "parts") (part "Pin"))
    )
    (comp (ref "TP135")
      (value "Pin")
      (footprint "Pin")
      (description "Testing pin")
      (libsource (lib "parts") (part "Pin"))
    )
    (comp (ref "TP136")
      (value "Pin")
      (footprint "Pin")
      (description "Testing pin")
      (libsource (lib "parts") (part "Pin"))
    )
    (comp (ref "TP137")
      (value "Pin")
      (footprint "Pin")
      (description "Testing pin")
      (libsource (lib "parts") (part "Pin"))
    )
    (comp (ref "TP138")
      (value "Pin")
      (footprint "Pin")
      (description "Testing pin")
      (libsource (lib "parts") (part "Pin"))
    )
    (comp (ref "TP139")
      (value "Pin")
      (footprint "Pin")
      (description "Testing pin")
      (libsource (lib "parts") (part "Pin"))
    )
    (comp (ref "TP140")
      (value "Pin")
      (footprint "Pin")
      (description "Testing pin")
      (libsource (lib "parts") (part "Pin"))
    )
    (comp (ref "TP141")
      (value "Pin")
      (footprint "Pin")
      (description "Testing pin")
      (libsource (lib "parts") (part "Pin"))
    )
    (comp (ref "TP142")
      (value "Pin")
      (footprint "Pin")
      (description "Testing pin")
      (libsource (lib "parts") (part "Pin"))
    )
    (comp (ref "TP143")
      (value "Pin")
      (footprint "Pin")
      (description "Testing pin")
      (libsource (lib "parts") (part "Pin"))
    )
    (comp (ref "TP144")
      (value "Pin")
      (footprint "Pin")
      (description "Testing pin")
      (libsource (lib "parts") (part "Pin"))
    )
    (comp (ref "TP145")
      (value "Pin")
      (footprint "Pin")
      (description "Testing pin")
      (libsource (lib "parts") (part "Pin"))
    )
    (comp (ref "TP146")
      (value "Pin")
      (footprint "Pin")
      (description "Testing pin")
      (libsource (lib "parts") (part "Pin"))
    )
    (comp (ref "TP147")
      (value "Pin")
      (footprint "Pin")
      (description "Testing pin")
      (libsource (lib "parts") (part "Pin"))
    )
    (comp (ref "TP148")
      (value "Pin")
      (footprint "Pin")
      (description "Testing pin")
      (libsource (lib "parts") (part "Pin"))
    )
    (comp (ref "TP149")
      (value "Pin")
      (footprint "Pin")
      (description "Testing pin")
      (libsource (lib "parts") (part "Pin"))
    )
    (comp (ref "TP150")
      (value "Pin")
      (footprint "Pin")
      (description "Testing pin")
      (libsource (lib "parts") (part "Pin"))
    )
    (comp (ref "U1")
      (value "PTH08T231W")
      (footprint "PTH08T231W")
      (libsource (lib "parts") (part "PTH08T231W"))
    )
    (comp (ref "U2") (value "7805S") (footprint "TO-263-3") (libsource (lib "parts") (part "7805S")))
  )
  (nets
    (net (code "1") (name "+5") (class "Default")
      (node (ref "C4") (pin "2") (pinfunction "2_2") (pintype "passive"))
      (node (ref "C5") (pin "2") (pinfunction "2_2") (pintype "passive"))
      (node (ref "C7") (pin "2") (pinfunction "2_2") (pintype "passive"))
      (node (ref "D1") (pin "2") (pinfunction "K_2") (pintype "passive"))
      (node (ref "D2") (pin "2") (pinfunction "K_2") (pintype "passive"))
      (node (ref "D3") (pin "2") (pinfunction "K_2") (pintype "passive"))
      (node (ref "D4") (pin "2") (pinfunction "K_2") (pintype "passive"))
      (node (ref "D5") (pin "2") (pinfunction "K_2") (pintype "passive"))
      (node (ref "K1") (pin "3") (pinfunction "3_3") (pintype "passive"))
      (node (ref "K10") (pin "3") (pinfunction "3_3") (pintype "passive"))
      (node (ref "K11") (pin "3") (pinfunction "3_3") (pintype "passive"))
      (node (ref "K12") (pin "3") (pinfunction "3_3") (pintype "passive"))
      (node (ref "K13") (pin "1") (pinfunction "1_1") (pintype "passive"))
      (node (ref "K13") (pin "3") (pinfunction "3_3") (pintype "passive"))
      (node (ref "K2") (pin "3") (pinfunction "3_3") (pintype "passive"))
      (node (ref "K3") (pin "3") (pinfunction "3_3") (pintype "passive"))
      (node (ref "K4") (pin "3") (pinfunction "3_3") (pintype "passive"))
      (node (ref "K5") (pin "3") (pinfunction "3_3") (pintype "passive"))
      (node (ref "K6") (pin "3") (pinfunction "3_3") (pintype "passive"))
      (node (ref "K7") (pin "3") (pinfunction "3_3") (pintype "passive"))
      (node (ref "K8") (pin "3") (pinfunction "3_3") (pintype "passive"))
      (node (ref "K9") (pin "3") (pinfunction "3_3") (pintype "passive"))
      (node (ref "U1") (pin "4") (pinfunction "VO_4") (pintype "passive"))
      (node (ref "U1") (pin "5") (pinfunction "Sense+_5") (pintype "passive"))
      (node (ref "U2") (pin "3") (pinfunction "OUTPUT_3") (pintype "passive"))
    )
    (net (code "2") (name "+10") (class "Default")
      (node (ref "C1") (pin "2") (pinfunction "2_2") (pintype "passive"))
      (node (ref "C2") (pin "2") (pinfunction "2_2") (pintype "passive"))
      (node (ref "C3") (pin "2") (pinfunction "2_2") (pintype "passive"))
      (node (ref "C6") (pin "2") (pinfunction "2_2") (pintype "passive"))
      (node (ref "P2") (pin "1") (pinfunction "1_1") (pintype "passive"))
      (node (ref "TP83") (pin "1") (pinfunction "Pin_1") (pintype "passive"))
      (node (ref "U1") (pin "2") (pinfunction "VI_2") (pintype "passive"))
      (node (ref "U1") (pin "9") (pinfunction "Track_9") (pintype "passive"))
      (node (ref "U2") (pin "1") (pinfunction "INPUT_1") (pintype "passive"))
    )
    (net (code "3") (name "/5V") (class "Default")
      (node (ref "CON1") (pin "1") (pinfunction "1_1") (pintype "passive"))
      (node (ref "TP145") (pin "1") (pinfunction "Pin_1") (pintype "passive"))
    )
    (net (code "4") (name "/CHG_EN") (class "Default")
      (node (ref "D5") (pin "1") (pinfunction "A_1") (pintype "passive"))
      (node (ref "K13") (pin "4") (pinfunction "4_4") (pintype "passive"))
      (node (ref "Q5") (pin "3") (pinfunction "C_3") (pintype "passive"))
    )
    (net (code "5") (name "/MOTOR_ENC_INPUT") (class "Default")
      (node (ref "K1") (pin "1") (pinfunction "1_1") (pintype "passive"))
      (node (ref "K10") (pin "1") (pinfunction "1_1") (pintype "passive"))
      (node (ref "K11") (pin "1") (pinfunction "1_1") (pintype "passive"))
      (node (ref "K12") (pin "1") (pinfunction "1_1") (pintype "passive"))
      (node (ref "K2") (pin "1") (pinfunction "1_1") (pintype "passive"))
      (node (ref "K3") (pin "1") (pinfunction "1_1") (pintype "passive"))
      (node (ref "K4") (pin "1") (pinfunction "1_1") (pintype "passive"))
      (node (ref "K5") (pin "1") (pinfunction "1_1") (pintype "passive"))
      (node (ref "K6") (pin "1") (pinfunction "1_1") (pintype "passive"))
      (node (ref "K7") (pin "1") (pinfunction "1_1") (pintype "passive"))
      (node (ref "K8") (pin "1") (pinfunction "1_1") (pintype "passive"))
      (node (ref "K9") (pin "1") (pinfunction "1_1") (pintype "passive"))
      (node (ref "TP106") (pin "1") (pinfunction "Pin_1") (pintype "passive"))
    )
    (net (code "6") (name "/RESET") (class "Default")
      (node (ref "P3") (pin "15") (pinfunction "15_15") (pintype "passive"))
      (node (ref "TP29") (pin "1") (pinfunction "Pin_1") (pintype "passive"))
    )
    (net (code "7") (name "/SPK+") (class "Default")
      (node (ref "CON1") (pin "4") (pinfunction "4_4") (pintype "passive"))
      (node (ref "TP148") (pin "1") (pinfunction "Pin_1") (pintype "passive"))
    )
    (net (code "8") (name "/SPK-") (class "Default")
      (node (ref "CON1") (pin "5") (pinfunction "5_5") (pintype "passive"))
      (node (ref "TP149") (pin "1") (pinfunction "Pin_1") (pintype "passive"))
    )
    (net (code "9") (name "/SWCLK") (class "Default")
      (node (ref "P3") (pin "9") (pinfunction "9_9") (pintype "passive"))
      (node (ref "TP20") (pin "1") (pinfunction "Pin_1") (pintype "passive"))
    )
    (net (code "10") (name "/SWDIO") (class "Default")
      (node (ref "P3") (pin "7") (pinfunction "7_7") (pintype "passive"))
      (node (ref "TP26") (pin "1") (pinfunction "Pin_1") (pintype "passive"))
    )
    (net (code "11") (name "/VTref") (class "Default")
      (node (ref "P3") (pin "1") (pinfunction "1_1") (pintype "passive"))
      (node (ref "TP17") (pin "1") (pinfunction "Pin_1") (pintype "passive"))
    )
    (net (code "12") (name "/WS2812_D") (class "Default")
      (node (ref "CON1") (pin "2") (pinfunction "2_2") (pintype "passive"))
      (node (ref "TP146") (pin "1") (pinfunction "Pin_1") (pintype "passive"))
    )
    (net (code "13") (name "GND") (class "Default")
      (node (ref "C1") (pin "1") (pinfunction "1_1") (pintype "passive"))
      (node (ref "C2") (pin "1") (pinfunction "1_1") (pintype "passive"))
      (node (ref "C3") (pin "1") (pinfunction "1_1") (pintype "passive"))
      (node (ref "C4") (pin "1") (pinfunction "1_1") (pintype "passive"))
      (node (ref "C5") (pin "1") (pinfunction "1_1") (pintype "passive"))
      (node (ref "C6") (pin "1") (pinfunction "1_1") (pintype "passive"))
      (node (ref "C7") (pin "1") (pinfunction "1_1") (pintype "passive"))
      (node (ref "CON1") (pin "3") (pinfunction "3_3") (pintype "passive"))
      (node (ref "CON1") (pin "SH") (pinfunction "SH_SH") (pintype "passive"))
      (node (ref "P1") (pin "16") (pinfunction "16_16") (pintype "passive"))
      (node (ref "P2") (pin "2") (pinfunction "2_2") (pintype "passive"))
      (node (ref "P3") (pin "10") (pinfunction "10_10") (pintype "passive"))
      (node (ref "P3") (pin "12") (pinfunction "12_12") (pintype "passive"))
      (node (ref "P3") (pin "4") (pinfunction "4_4") (pintype "passive"))
      (node (ref "P3") (pin "6") (pinfunction "6_6") (pintype "passive"))
      (node (ref "P3") (pin "8") (pinfunction "8_8") (pintype "passive"))
      (node (ref "P4") (pin "2") (pinfunction "2_2") (pintype "passive"))
      (node (ref "Q1") (pin "2") (pinfunction "E_2") (pintype "passive"))
      (node (ref "Q2") (pin "2") (pinfunction "E_2") (pintype "passive"))
      (node (ref "Q3") (pin "2") (pinfunction "E_2") (pintype "passive"))
      (node (ref "Q4") (pin "2") (pinfunction "E_2") (pintype "passive"))
      (node (ref "Q5") (pin "2") (pinfunction "E_2") (pintype "passive"))
      (node (ref "R12") (pin "1") (pinfunction "1_1") (pintype "passive"))
      (node (ref "R5") (pin "1") (pinfunction "1_1") (pintype "passive"))
      (node (ref "R6") (pin "1") (pinfunction "1_1") (pintype "passive"))
      (node (ref "TP147") (pin "1") (pinfunction "Pin_1") (pintype "passive"))
      (node (ref "TP23") (pin "1") (pinfunction "Pin_1") (pintype "passive"))
      (node (ref "TP94") (pin "1") (pinfunction "Pin_1") (pintype "passive"))
      (node (ref "U1") (pin "3") (pinfunction "GND_3") (pintype "passive"))
      (node (ref "U1") (pin "6") (pinfunction "Sense-_6") (pintype "passive"))
      (node (ref "U2") (pin "2") (pinfunction "GND_2") (pintype "passive"))
      (node (ref "U2") (pin "4") (pinfunction "GND2_4") (pintype "passive"))
    )
    (net (code "14") (name "Net-(D1-A)") (class "Default")
      (node (ref "D1") (pin "1") (pinfunction "A_1") (pintype "passive"))
      (node (ref "K1") (pin "4") (pinfunction "4_4") (pintype "passive"))
      (node (ref "K5") (pin "4") (pinfunction "4_4") (pintype "passive"))
      (node (ref "K9") (pin "4") (pinfunction "4_4") (pintype "passive"))
      (node (ref "Q1") (pin "3") (pinfunction "C_3") (pintype "passive"))
    )
    (net (code "15") (name "Net-(D2-A)") (class "Default")
      (node (ref "D2") (pin "1") (pinfunction "A_1") (pintype "passive"))
      (node (ref "K10") (pin "4") (pinfunction "4_4") (pintype "passive"))
      (node (ref "K2") (pin "4") (pinfunction "4_4") (pintype "passive"))
      (node (ref "K6") (pin "4") (pinfunction "4_4") (pintype "passive"))
      (node (ref "Q2") (pin "3") (pinfunction "C_3") (pintype "passive"))
    )
    (net (code "16") (name "Net-(D3-A)") (class "Default")
      (node (ref "D3") (pin "1") (pinfunction "A_1") (pintype "passive"))
      (node (ref "K11") (pin "4") (pinfunction "4_4") (pintype "passive"))
      (node (ref "K3") (pin "4") (pinfunction "4_4") (pintype "passive"))
      (node (ref "K7") (pin "4") (pinfunction "4_4") (pintype "passive"))
      (node (ref "Q3") (pin "3") (pinfunction "C_3") (pintype "passive"))
    )
    (net (code "17") (name "Net-(D4-A)") (class "Default")
      (node (ref "D4") (pin "1") (pinfunction "A_1") (pintype "passive"))
      (node (ref "K12") (pin "4") (pinfunction "4_4") (pintype "passive"))
      (node (ref "K4") (pin "4") (pinfunction "4_4") (pintype "passive"))
      (node (ref "K8") (pin "4") (pinfunction "4_4") (pintype "passive"))
      (node (ref "Q4") (pin "3") (pinfunction "C_3") (pintype "passive"))
    )
    (net (code "18") (name "Net-(Q1-B)") (class "Default")
      (node (ref "Q1") (pin "1") (pinfunction "B_1") (pintype "passive"))
      (node (ref "R7") (pin "2") (pinfunction "2_2") (pintype "passive"))
    )
    (net (code "19") (name "Net-(Q2-B)") (class "Default")
      (node (ref "Q2") (pin "1") (pinfunction "B_1") (pintype "passive"))
      (node (ref "R8") (pin "2") (pinfunction "2_2") (pintype "passive"))
    )
    (net (code "20") (name "Net-(Q3-B)") (class "Default")
      (node (ref "Q3") (pin "1") (pinfunction "B_1") (pintype "passive"))
      (node (ref "R9") (pin "2") (pinfunction "2_2") (pintype "passive"))
    )
    (net (code "21") (name "Net-(Q4-B)") (class "Default")
      (node (ref "Q4") (pin "1") (pinfunction "B_1") (pintype "passive"))
      (node (ref "R10") (pin "2") (pinfunction "2_2") (pintype "passive"))
    )
    (net (code "22") (name "Net-(Q5-B)") (class "Default")
      (node (ref "Q5") (pin "1") (pinfunction "B_1") (pintype "passive"))
      (node (ref "R14") (pin "2") (pinfunction "2_2") (pintype "passive"))
    )
    (net (code "23") (name "Net-(TP34-Pin)") (class "Default")
      (node (ref "K1") (pin "2") (pinfunction "2_2") (pintype "passive"))
      (node (ref "TP34") (pin "1") (pinfunction "Pin_1") (pintype "passive"))
    )
    (net (code "24") (name "Net-(TP36-Pin)") (class "Default")
      (node (ref "R1") (pin "1") (pinfunction "1_1") (pintype "passive"))
      (node (ref "TP36") (pin "1") (pinfunction "Pin_1") (pintype "passive"))
    )
    (net (code "25") (name "Net-(TP37-Pin)") (class "Default")
      (node (ref "P1") (pin "12") (pinfunction "12_12") (pintype "passive"))
      (node (ref "TP37") (pin "1") (pinfunction "Pin_1") (pintype "passive"))
    )
    (net (code "26") (name "Net-(TP38-Pin)") (class "Default")
      (node (ref "K5") (pin "2") (pinfunction "2_2") (pintype "passive"))
      (node (ref "TP38") (pin "1") (pinfunction "Pin_1") (pintype "passive"))
    )
    (net (code "27") (name "Net-(TP40-Pin)") (class "Default")
      (node (ref "R1") (pin "2") (pinfunction "2_2") (pintype "passive"))
      (node (ref "TP40") (pin "1") (pinfunction "Pin_1") (pintype "passive"))
    )
    (net (code "28") (name "Net-(TP42-Pin)") (class "Default")
      (node (ref "K9") (pin "2") (pinfunction "2_2") (pintype "passive"))
      (node (ref "TP42") (pin "1") (pinfunction "Pin_1") (pintype "passive"))
    )
    (net (code "29") (name "Net-(TP44-Pin)") (class "Default")
      (node (ref "R2") (pin "1") (pinfunction "1_1") (pintype "passive"))
      (node (ref "TP44") (pin "1") (pinfunction "Pin_1") (pintype "passive"))
    )
    (net (code "30") (name "Net-(TP45-Pin)") (class "Default")
      (node (ref "P1") (pin "13") (pinfunction "13_13") (pintype "passive"))
      (node (ref "TP45") (pin "1") (pinfunction "Pin_1") (pintype "passive"))
    )
    (net (code "31") (name "Net-(TP46-Pin)") (class "Default")
      (node (ref "K2") (pin "2") (pinfunction "2_2") (pintype "passive"))
      (node (ref "TP46") (pin "1") (pinfunction "Pin_1") (pintype "passive"))
    )
    (net (code "32") (name "Net-(TP48-Pin)") (class "Default")
      (node (ref "R2") (pin "2") (pinfunction "2_2") (pintype "passive"))
      (node (ref "TP48") (pin "1") (pinfunction "Pin_1") (pintype "passive"))
    )
    (net (code "33") (name "Net-(TP50-Pin)") (class "Default")
      (node (ref "K6") (pin "2") (pinfunction "2_2") (pintype "passive"))
      (node (ref "TP50") (pin "1") (pinfunction "Pin_1") (pintype "passive"))
    )
    (net (code "34") (name "Net-(TP52-Pin)") (class "Default")
      (node (ref "R3") (pin "1") (pinfunction "1_1") (pintype "passive"))
      (node (ref "TP52") (pin "1") (pinfunction "Pin_1") (pintype "passive"))
    )
    (net (code "35") (name "Net-(TP53-Pin)") (class "Default")
      (node (ref "P1") (pin "14") (pinfunction "14_14") (pintype "passive"))
      (node (ref "TP53") (pin "1") (pinfunction "Pin_1") (pintype "passive"))
    )
    (net (code "36") (name "Net-(TP54-Pin)") (class "Default")
      (node (ref "K10") (pin "2") (pinfunction "2_2") (pintype "passive"))
      (node (ref "TP54") (pin "1") (pinfunction "Pin_1") (pintype "passive"))
    )
    (net (code "37") (name "Net-(TP56-Pin)") (class "Default")
      (node (ref "R3") (pin "2") (pinfunction "2_2") (pintype "passive"))
      (node (ref "TP56") (pin "1") (pinfunction "Pin_1") (pintype "passive"))
    )
    (net (code "38") (name "Net-(TP58-Pin)") (class "Default")
      (node (ref "K3") (pin "2") (pinfunction "2_2") (pintype "passive"))
      (node (ref "TP58") (pin "1") (pinfunction "Pin_1") (pintype "passive"))
    )
    (net (code "39") (name "Net-(TP60-Pin)") (class "Default")
      (node (ref "R4") (pin "1") (pinfunction "1_1") (pintype "passive"))
      (node (ref "TP60") (pin "1") (pinfunction "Pin_1") (pintype "passive"))
    )
    (net (code "40") (name "Net-(TP61-Pin)") (class "Default")
      (node (ref "P1") (pin "11") (pinfunction "11_11") (pintype "passive"))
      (node (ref "TP61") (pin "1") (pinfunction "Pin_1") (pintype "passive"))
    )
    (net (code "41") (name "Net-(TP62-Pin)") (class "Default")
      (node (ref "K7") (pin "2") (pinfunction "2_2") (pintype "passive"))
      (node (ref "TP62") (pin "1") (pinfunction "Pin_1") (pintype "passive"))
    )
    (net (code "42") (name "Net-(TP64-Pin)") (class "Default")
      (node (ref "R4") (pin "2") (pinfunction "2_2") (pintype "passive"))
      (node (ref "TP64") (pin "1") (pinfunction "Pin_1") (pintype "passive"))
    )
    (net (code "43") (name "Net-(TP66-Pin)") (class "Default")
      (node (ref "K11") (pin "2") (pinfunction "2_2") (pintype "passive"))
      (node (ref "TP66") (pin "1") (pinfunction "Pin_1") (pintype "passive"))
    )
    (net (code "44") (name "Net-(TP68-Pin)") (class "Default")
      (node (ref "R11") (pin "1") (pinfunction "1_1") (pintype "passive"))
      (node (ref "TP68") (pin "1") (pinfunction "Pin_1") (pintype "passive"))
    )
    (net (code "45") (name "Net-(TP69-Pin)") (class "Default")
      (node (ref "P1") (pin "10") (pinfunction "10_10") (pintype "passive"))
      (node (ref "TP69") (pin "1") (pinfunction "Pin_1") (pintype "passive"))
    )
    (net (code "46") (name "Net-(TP70-Pin)") (class "Default")
      (node (ref "K4") (pin "2") (pinfunction "2_2") (pintype "passive"))
      (node (ref "TP70") (pin "1") (pinfunction "Pin_1") (pintype "passive"))
    )
    (net (code "47") (name "Net-(TP72-Pin)") (class "Default")
      (node (ref "R11") (pin "2") (pinfunction "2_2") (pintype "passive"))
      (node (ref "TP72") (pin "1") (pinfunction "Pin_1") (pintype "passive"))
    )
    (net (code "48") (name "Net-(TP74-Pin)") (class "Default")
      (node (ref "K8") (pin "2") (pinfunction "2_2") (pintype "passive"))
      (node (ref "TP74") (pin "1") (pinfunction "Pin_1") (pintype "passive"))
    )
    (net (code "49") (name "Net-(TP76-Pin)") (class "Default")
      (node (ref "R13") (pin "1") (pinfunction "1_1") (pintype "passive"))
      (node (ref "TP76") (pin "1") (pinfunction "Pin_1") (pintype "passive"))
    )
    (net (code "50") (name "Net-(TP77-Pin)") (class "Default")
      (node (ref "P1") (pin "9") (pinfunction "9_9") (pintype "passive"))
      (node (ref "TP77") (pin "1") (pinfunction "Pin_1") (pintype "passive"))
    )
    (net (code "51") (name "Net-(TP78-Pin)") (class "Default")
      (node (ref "K12") (pin "2") (pinfunction "2_2") (pintype "passive"))
      (node (ref "TP78") (pin "1") (pinfunction "Pin_1") (pintype "passive"))
    )
    (net (code "52") (name "Net-(TP80-Pin)") (class "Default")
      (node (ref "R13") (pin "2") (pinfunction "2_2") (pintype "passive"))
      (node (ref "TP80") (pin "1") (pinfunction "Pin_1") (pintype "passive"))
    )
    (net (code "53") (name "Net-(TP88-Pin)") (class "Default")
      (node (ref "P1") (pin "15") (pinfunction "15_15") (pintype "passive"))
      (node (ref "TP88") (pin "1") (pinfunction "Pin_1") (pintype "passive"))
    )
    (net (code "54") (name "Net-(TP91-Pin)") (class "Default")
      (node (ref "K13") (pin "2") (pinfunction "2_2") (pintype "passive"))
      (node (ref "TP91") (pin "1") (pinfunction "Pin_1") (pintype "passive"))
    )
    (net (code "55") (name "Net-(TP92-Pin)") (class "Default")
      (node (ref "TP92") (pin "1") (pinfunction "Pin_1") (pintype "passive"))
      (node (ref "TP99") (pin "1") (pinfunction "Pin_1") (pintype "passive"))
    )
    (net (code "56") (name "Net-(TP98-Pin)") (class "Default")
      (node (ref "R14") (pin "1") (pinfunction "1_1") (pintype "passive"))
      (node (ref "TP98") (pin "1") (pinfunction "Pin_1") (pintype "passive"))
    )
    (net (code "57") (name "Net-(TP100-Pin)") (class "Default")
      (node (ref "TP100") (pin "1") (pinfunction "Pin_1") (pintype "passive"))
      (node (ref "TP93") (pin "1") (pinfunction "Pin_1") (pintype "passive"))
    )
    (net (code "58") (name "Net-(TP101-Pin)") (class "Default")
      (node (ref "TP101") (pin "1") (pinfunction "Pin_1") (pintype "passive"))
      (node (ref "TP97") (pin "1") (pinfunction "Pin_1") (pintype "passive"))
    )
    (net (code "59") (name "Net-(TP103-Pin)") (class "Default")
      (node (ref "R10") (pin "1") (pinfunction "1_1") (pintype "passive"))
      (node (ref "R12") (pin "2") (pinfunction "2_2") (pintype "passive"))
      (node (ref "R7") (pin "1") (pinfunction "1_1") (pintype "passive"))
      (node (ref "R8") (pin "1") (pinfunction "1_1") (pintype "passive"))
      (node (ref "R9") (pin "1") (pinfunction "1_1") (pintype "passive"))
      (node (ref "TP103") (pin "1") (pinfunction "Pin_1") (pintype "passive"))
    )
    (net (code "60") (name "Net-(TP104-Pin)") (class "Default")
      (node (ref "TP104") (pin "1") (pinfunction "Pin_1") (pintype "passive"))
      (node (ref "TP105") (pin "1") (pinfunction "Pin_1") (pintype "passive"))
    )
    (net (code "61") (name "Net-(TP107-Pin)") (class "Default")
      (node (ref "P1") (pin "8") (pinfunction "8_8") (pintype "passive"))
      (node (ref "TP107") (pin "1") (pinfunction "Pin_1") (pintype "passive"))
    )
    (net (code "62") (name "Net-(TP108-Pin)") (class "Default")
      (node (ref "TP108") (pin "1") (pinfunction "Pin_1") (pintype "passive"))
      (node (ref "TP110") (pin "1") (pinfunction "Pin_1") (pintype "passive"))
    )
    (net (code "63") (name "Net-(TP109-Pin)") (class "Default")
      (node (ref "P1") (pin "4") (pinfunction "4_4") (pintype "passive"))
      (node (ref "TP109") (pin "1") (pinfunction "Pin_1") (pintype "passive"))
    )
    (net (code "64") (name "Net-(TP111-Pin)") (class "Default")
      (node (ref "TP111") (pin "1") (pinfunction "Pin_1") (pintype "passive"))
      (node (ref "TP112") (pin "1") (pinfunction "Pin_1") (pintype "passive"))
      (node (ref "TP113") (pin "1") (pinfunction "Pin_1") (pintype "passive"))
    )
    (net (code "65") (name "Net-(TP116-Pin)") (class "Default")
      (node (ref "P1") (pin "7") (pinfunction "7_7") (pintype "passive"))
      (node (ref "TP116") (pin "1") (pinfunction "Pin_1") (pintype "passive"))
    )
    (net (code "66") (name "Net-(TP117-Pin)") (class "Default")
      (node (ref "TP117") (pin "1") (pinfunction "Pin_1") (pintype "passive"))
      (node (ref "TP119") (pin "1") (pinfunction "Pin_1") (pintype "passive"))
    )
    (net (code "67") (name "Net-(TP118-Pin)") (class "Default")
      (node (ref "P1") (pin "3") (pinfunction "3_3") (pintype "passive"))
      (node (ref "TP118") (pin "1") (pinfunction "Pin_1") (pintype "passive"))
    )
    (net (code "68") (name "Net-(TP120-Pin)") (class "Default")
      (node (ref "TP120") (pin "1") (pinfunction "Pin_1") (pintype "passive"))
      (node (ref "TP121") (pin "1") (pinfunction "Pin_1") (pintype "passive"))
      (node (ref "TP122") (pin "1") (pinfunction "Pin_1") (pintype "passive"))
    )
    (net (code "69") (name "Net-(TP125-Pin)") (class "Default")
      (node (ref "P1") (pin "6") (pinfunction "6_6") (pintype "passive"))
      (node (ref "TP125") (pin "1") (pinfunction "Pin_1") (pintype "passive"))
    )
    (net (code "70") (name "Net-(TP126-Pin)") (class "Default")
      (node (ref "TP126") (pin "1") (pinfunction "Pin_1") (pintype "passive"))
      (node (ref "TP128") (pin "1") (pinfunction "Pin_1") (pintype "passive"))
    )
    (net (code "71") (name "Net-(TP127-Pin)") (class "Default")
      (node (ref "P1") (pin "2") (pinfunction "2_2") (pintype "passive"))
      (node (ref "TP127") (pin "1") (pinfunction "Pin_1") (pintype "passive"))
    )
    (net (code "72") (name "Net-(TP129-Pin)") (class "Default")
      (node (ref "TP129") (pin "1") (pinfunction "Pin_1") (pintype "passive"))
      (node (ref "TP130") (pin "1") (pinfunction "Pin_1") (pintype "passive"))
      (node (ref "TP131") (pin "1") (pinfunction "Pin_1") (pintype "passive"))
    )
    (net (code "73") (name "Net-(TP134-Pin)") (class "Default")
      (node (ref "P1") (pin "5") (pinfunction "5_5") (pintype "passive"))
      (node (ref "TP134") (pin "1") (pinfunction "Pin_1") (pintype "passive"))
    )
    (net (code "74") (name "Net-(TP135-Pin)") (class "Default")
      (node (ref "TP135") (pin "1") (pinfunction "Pin_1") (pintype "passive"))
      (node (ref "TP137") (pin "1") (pinfunction "Pin_1") (pintype "passive"))
    )
    (net (code "75") (name "Net-(TP136-Pin)") (class "Default")
      (node (ref "P1") (pin "1") (pinfunction "1_1") (pintype "passive"))
      (node (ref "TP136") (pin "1") (pinfunction "Pin_1") (pintype "passive"))
    )
    (net (code "76") (name "Net-(TP138-Pin)") (class "Default")
      (node (ref "TP138") (pin "1") (pinfunction "Pin_1") (pintype "passive"))
      (node (ref "TP139") (pin "1") (pinfunction "Pin_1") (pintype "passive"))
      (node (ref "TP140") (pin "1") (pinfunction "Pin_1") (pintype "passive"))
    )
    (net (code "77") (name "Net-(U1-UVLO)") (class "Default")
      (node (ref "R5") (pin "2") (pinfunction "2_2") (pintype "passive"))
      (node (ref "U1") (pin "10") (pinfunction "UVLO_10") (pintype "passive"))
    )
    (net (code "78") (name "Net-(U1-VoAdj)") (class "Default")
      (node (ref "R6") (pin "2") (pinfunction "2_2") (pintype "passive"))
      (node (ref "U1") (pin "7") (pinfunction "VoAdj_7") (pintype "passive"))
    )
    (net (code "79") (name "VBAT") (class "Default")
      (node (ref "P4") (pin "1") (pinfunction "1_1") (pintype "passive"))
      (node (ref "TP84") (pin "1") (pinfunction "Pin_1") (pintype "passive"))
    )
    (net (code "80") (name "unconnected-(P3-Pad2)") (class "Default")
      (node (ref "P3") (pin "2") (pinfunction "2_2") (pintype "passive+no_connect"))
    )
    (net (code "81") (name "unconnected-(P3-Pad3)") (class "Default")
      (node (ref "P3") (pin "3") (pinfunction "3_3") (pintype "passive+no_connect"))
    )
    (net (code "82") (name "unconnected-(P3-Pad5)") (class "Default")
      (node (ref "P3") (pin "5") (pinfunction "5_5") (pintype "passive"))
    )
    (net (code "83") (name "unconnected-(P3-Pad11)") (class "Default")
      (node (ref "P3") (pin "11") (pinfunction "11_11") (pintype "passive+no_connect"))
    )
    (net (code "84") (name "unconnected-(P3-Pad13)") (class "Default")
      (node (ref "P3") (pin "13") (pinfunction "13_13") (pintype "passive+no_connect"))
    )
    (net (code "85") (name "unconnected-(P3-Pad14)") (class "Default")
      (node (ref "P3") (pin "14") (pinfunction "14_14") (pintype "passive+no_connect"))
    )
    (net (code "86") (name "unconnected-(P3-Pad16)") (class "Default")
      (node (ref "P3") (pin "16") (pinfunction "16_16") (pintype "passive+no_connect"))
    )
    (net (code "87") (name "unconnected-(P3-Pad17)") (class "Default")
      (node (ref "P3") (pin "17") (pinfunction "17_17") (pintype "passive+no_connect"))
    )
    (net (code "88") (name "unconnected-(P3-Pad18)") (class "Default")
      (node (ref "P3") (pin "18") (pinfunction "18_18") (pintype "passive+no_connect"))
    )
    (net (code "89") (name "unconnected-(P3-Pad19)") (class "Default")
      (node (ref "P3") (pin "19") (pinfunction "19_19") (pintype "passive+no_connect"))
    )
    (net (code "90") (name "unconnected-(P3-Pad20)") (class "Default")
      (node (ref "P3") (pin "20") (pinfunction "20_20") (pintype "passive+no_connect"))
    )
    (net (code "91") (name "unconnected-(TP1-Pin-Pad1)") (class "Default")
      (node (ref "TP1") (pin "1") (pinfunction "Pin_1") (pintype "passive"))
    )
    (net (code "92") (name "unconnected-(TP2-Pin-Pad1)") (class "Default")
      (node (ref "TP2") (pin "1") (pinfunction "Pin_1") (pintype "passive"))
    )
    (net (code "93") (name "unconnected-(TP3-Pin-Pad1)") (class "Default")
      (node (ref "TP3") (pin "1") (pinfunction "Pin_1") (pintype "passive"))
    )
    (net (code "94") (name "unconnected-(TP4-Pin-Pad1)") (class "Default")
      (node (ref "TP4") (pin "1") (pinfunction "Pin_1") (pintype "passive"))
    )
    (net (code "95") (name "unconnected-(TP5-Pin-Pad1)") (class "Default")
      (node (ref "TP5") (pin "1") (pinfunction "Pin_1") (pintype "passive"))
    )
    (net (code "96") (name "unconnected-(TP6-Pin-Pad1)") (class "Default")
      (node (ref "TP6") (pin "1") (pinfunction "Pin_1") (pintype "passive"))
    )
    (net (code "97") (name "unconnected-(TP7-Pin-Pad1)") (class "Default")
      (node (ref "TP7") (pin "1") (pinfunction "Pin_1") (pintype "passive"))
    )
    (net (code "98") (name "unconnected-(TP8-Pin-Pad1)") (class "Default")
      (node (ref "TP8") (pin "1") (pinfunction "Pin_1") (pintype "passive"))
    )
    (net (code "99") (name "unconnected-(TP9-Pin-Pad1)") (class "Default")
      (node (ref "TP9") (pin "1") (pinfunction "Pin_1") (pintype "passive"))
    )
    (net (code "100") (name "unconnected-(TP10-Pin-Pad1)") (class "Default")
      (node (ref "TP10") (pin "1") (pinfunction "Pin_1") (pintype "passive"))
    )
    (net (code "101") (name "unconnected-(TP11-Pin-Pad1)") (class "Default")
      (node (ref "TP11") (pin "1") (pinfunction "Pin_1") (pintype "passive"))
    )
    (net (code "102") (name "unconnected-(TP12-Pin-Pad1)") (class "Default")
      (node (ref "TP12") (pin "1") (pinfunction "Pin_1") (pintype "passive"))
    )
    (net (code "103") (name "unconnected-(TP13-Pin-Pad1)") (class "Default")
      (node (ref "TP13") (pin "1") (pinfunction "Pin_1") (pintype "passive"))
    )
    (net (code "104") (name "unconnected-(TP14-Pin-Pad1)") (class "Default")
      (node (ref "TP14") (pin "1") (pinfunction "Pin_1") (pintype "passive"))
    )
    (net (code "105") (name "unconnected-(TP15-Pin-Pad1)") (class "Default")
      (node (ref "TP15") (pin "1") (pinfunction "Pin_1") (pintype "passive"))
    )
    (net (code "106") (name "unconnected-(TP16-Pin-Pad1)") (class "Default")
      (node (ref "TP16") (pin "1") (pinfunction "Pin_1") (pintype "passive"))
    )
    (net (code "107") (name "unconnected-(TP18-Pin-Pad1)") (class "Default")
      (node (ref "TP18") (pin "1") (pinfunction "Pin_1") (pintype "passive"))
    )
    (net (code "108") (name "unconnected-(TP19-Pin-Pad1)") (class "Default")
      (node (ref "TP19") (pin "1") (pinfunction "Pin_1") (pintype "passive"))
    )
    (net (code "109") (name "unconnected-(TP21-Pin-Pad1)") (class "Default")
      (node (ref "TP21") (pin "1") (pinfunction "Pin_1") (pintype "passive"))
    )
    (net (code "110") (name "unconnected-(TP22-Pin-Pad1)") (class "Default")
      (node (ref "TP22") (pin "1") (pinfunction "Pin_1") (pintype "passive"))
    )
    (net (code "111") (name "unconnected-(TP24-Pin-Pad1)") (class "Default")
      (node (ref "TP24") (pin "1") (pinfunction "Pin_1") (pintype "passive"))
    )
    (net (code "112") (name "unconnected-(TP25-Pin-Pad1)") (class "Default")
      (node (ref "TP25") (pin "1") (pinfunction "Pin_1") (pintype "passive"))
    )
    (net (code "113") (name "unconnected-(TP27-Pin-Pad1)") (class "Default")
      (node (ref "TP27") (pin "1") (pinfunction "Pin_1") (pintype "passive"))
    )
    (net (code "114") (name "unconnected-(TP28-Pin-Pad1)") (class "Default")
      (node (ref "TP28") (pin "1") (pinfunction "Pin_1") (pintype "passive"))
    )
    (net (code "115") (name "unconnected-(TP30-Pin-Pad1)") (class "Default")
      (node (ref "TP30") (pin "1") (pinfunction "Pin_1") (pintype "passive"))
    )
    (net (code "116") (name "unconnected-(TP31-Pin-Pad1)") (class "Default")
      (node (ref "TP31") (pin "1") (pinfunction "Pin_1") (pintype "passive"))
    )
    (net (code "117") (name "unconnected-(TP32-Pin-Pad1)") (class "Default")
      (node (ref "TP32") (pin "1") (pinfunction "Pin_1") (pintype "passive"))
    )
    (net (code "118") (name "unconnected-(TP33-Pin-Pad1)") (class "Default")
      (node (ref "TP33") (pin "1") (pinfunction "Pin_1") (pintype "passive"))
    )
    (net (code "119") (name "unconnected-(TP35-Pin-Pad1)") (class "Default")
      (node (ref "TP35") (pin "1") (pinfunction "Pin_1") (pintype "passive"))
    )
    (net (code "120") (name "unconnected-(TP39-Pin-Pad1)") (class "Default")
      (node (ref "TP39") (pin "1") (pinfunction "Pin_1") (pintype "passive"))
    )
    (net (code "121") (name "unconnected-(TP41-Pin-Pad1)") (class "Default")
      (node (ref "TP41") (pin "1") (pinfunction "Pin_1") (pintype "passive"))
    )
    (net (code "122") (name "unconnected-(TP43-Pin-Pad1)") (class "Default")
      (node (ref "TP43") (pin "1") (pinfunction "Pin_1") (pintype "passive"))
    )
    (net (code "123") (name "unconnected-(TP47-Pin-Pad1)") (class "Default")
      (node (ref "TP47") (pin "1") (pinfunction "Pin_1") (pintype "passive"))
    )
    (net (code "124") (name "unconnected-(TP49-Pin-Pad1)") (class "Default")
      (node (ref "TP49") (pin "1") (pinfunction "Pin_1") (pintype "passive"))
    )
    (net (code "125") (name "unconnected-(TP51-Pin-Pad1)") (class "Default")
      (node (ref "TP51") (pin "1") (pinfunction "Pin_1") (pintype "passive"))
    )
    (net (code "126") (name "unconnected-(TP55-Pin-Pad1)") (class "Default")
      (node (ref "TP55") (pin "1") (pinfunction "Pin_1") (pintype "passive"))
    )
    (net (code "127") (name "unconnected-(TP57-Pin-Pad1)") (class "Default")
      (node (ref "TP57") (pin "1") (pinfunction "Pin_1") (pintype "passive"))
    )
    (net (code "128") (name "unconnected-(TP59-Pin-Pad1)") (class "Default")
      (node (ref "TP59") (pin "1") (pinfunction "Pin_1") (pintype "passive"))
    )
    (net (code "129") (name "unconnected-(TP63-Pin-Pad1)") (class "Default")
      (node (ref "TP63") (pin "1") (pinfunction "Pin_1") (pintype "passive"))
    )
    (net (code "130") (name "unconnected-(TP65-Pin-Pad1)") (class "Default")
      (node (ref "TP65") (pin "1") (pinfunction "Pin_1") (pintype "passive"))
    )
    (net (code "131") (name "unconnected-(TP67-Pin-Pad1)") (class "Default")
      (node (ref "TP67") (pin "1") (pinfunction "Pin_1") (pintype "passive"))
    )
    (net (code "132") (name "unconnected-(TP71-Pin-Pad1)") (class "Default")
      (node (ref "TP71") (pin "1") (pinfunction "Pin_1") (pintype "passive"))
    )
    (net (code "133") (name "unconnected-(TP73-Pin-Pad1)") (class "Default")
      (node (ref "TP73") (pin "1") (pinfunction "Pin_1") (pintype "passive"))
    )
    (net (code "134") (name "unconnected-(TP75-Pin-Pad1)") (class "Default")
      (node (ref "TP75") (pin "1") (pinfunction "Pin_1") (pintype "passive"))
    )
    (net (code "135") (name "unconnected-(TP79-Pin-Pad1)") (class "Default")
      (node (ref "TP79") (pin "1") (pinfunction "Pin_1") (pintype "passive"))
    )
    (net (code "136") (name "unconnected-(TP81-Pin-Pad1)") (class "Default")
      (node (ref "TP81") (pin "1") (pinfunction "Pin_1") (pintype "passive"))
    )
    (net (code "137") (name "unconnected-(TP82-Pin-Pad1)") (class "Default")
      (node (ref "TP82") (pin "1") (pinfunction "Pin_1") (pintype "passive"))
    )
    (net (code "138") (name "unconnected-(TP85-Pin-Pad1)") (class "Default")
      (node (ref "TP85") (pin "1") (pinfunction "Pin_1") (pintype "passive"))
    )
    (net (code "139") (name "unconnected-(TP86-Pin-Pad1)") (class "Default")
      (node (ref "TP86") (pin "1") (pinfunction "Pin_1") (pintype "passive"))
    )
    (net (code "140") (name "unconnected-(TP87-Pin-Pad1)") (class "Default")
      (node (ref "TP87") (pin "1") (pinfunction "Pin_1") (pintype "passive"))
    )
    (net (code "141") (name "unconnected-(TP89-Pin-Pad1)") (class "Default")
      (node (ref "TP89") (pin "1") (pinfunction "Pin_1") (pintype "passive"))
    )
    (net (code "142") (name "unconnected-(TP90-Pin-Pad1)") (class "Default")
      (node (ref "TP90") (pin "1") (pinfunction "Pin_1") (pintype "passive"))
    )
    (net (code "143") (name "unconnected-(TP95-Pin-Pad1)") (class "Default")
      (node (ref "TP95") (pin "1") (pinfunction "Pin_1") (pintype "passive"))
    )
    (net (code "144") (name "unconnected-(TP96-Pin-Pad1)") (class "Default")
      (node (ref "TP96") (pin "1") (pinfunction "Pin_1") (pintype "passive"))
    )
    (net (code "145") (name "unconnected-(TP102-Pin-Pad1)") (class "Default")
      (node (ref "TP102") (pin "1") (pinfunction "Pin_1") (pintype "passive"))
    )
    (net (code "146") (name "unconnected-(TP114-Pin-Pad1)") (class "Default")
      (node (ref "TP114") (pin "1") (pinfunction "Pin_1") (pintype "passive"))
    )
    (net (code "147") (name "unconnected-(TP115-Pin-Pad1)") (class "Default")
      (node (ref "TP115") (pin "1") (pinfunction "Pin_1") (pintype "passive"))
    )
    (net (code "148") (name "unconnected-(TP123-Pin-Pad1)") (class "Default")
      (node (ref "TP123") (pin "1") (pinfunction "Pin_1") (pintype "passive"))
    )
    (net (code "149") (name "unconnected-(TP124-Pin-Pad1)") (class "Default")
      (node (ref "TP124") (pin "1") (pinfunction "Pin_1") (pintype "passive"))
    )
    (net (code "150") (name "unconnected-(TP132-Pin-Pad1)") (class "Default")
      (node (ref "TP132") (pin "1") (pinfunction "Pin_1") (pintype "passive"))
    )
    (net (code "151") (name "unconnected-(TP133-Pin-Pad1)") (class "Default")
      (node (ref "TP133") (pin "1") (pinfunction "Pin_1") (pintype "passive"))
    )
    (net (code "152") (name "unconnected-(TP141-Pin-Pad1)") (class "Default")
      (node (ref "TP141") (pin "1") (pinfunction "Pin_1") (pintype "passive"))
    )
    (net (code "153") (name "unconnected-(TP142-Pin-Pad1)") (class "Default")
      (node (ref "TP142") (pin "1") (pinfunction "Pin_1") (pintype "passive"))
    )
    (net (code "154") (name "unconnected-(TP143-Pin-Pad1)") (class "Default")
      (node (ref "TP143") (pin "1") (pinfunction "Pin_1") (pintype "passive"))
    )
    (net (code "155") (name "unconnected-(TP144-Pin-Pad1)") (class "Default")
      (node (ref "TP144") (pin "1") (pinfunction "Pin_1") (pintype "passive"))
    )
    (net (code "156") (name "unconnected-(TP150-Pin-Pad1)") (class "Default")
      (node (ref "TP150") (pin "1") (pinfunction "Pin_1") (pintype "passive"))
    )
    (net (code "157") (name "unconnected-(U1-Sync-Pad1)") (class "Default")
      (node (ref "U1") (pin "1") (pinfunction "Sync_1") (pintype "passive+no_connect"))
    )
    (net (code "158") (name "unconnected-(U1-TT-Pad8)") (class "Default")
      (node (ref "U1") (pin "8") (pinfunction "TT_8") (pintype "passive+no_connect"))
    )
  )
)
